# IoT_PCB.net
KiCad netlist of a schematic drawn in EAGLE
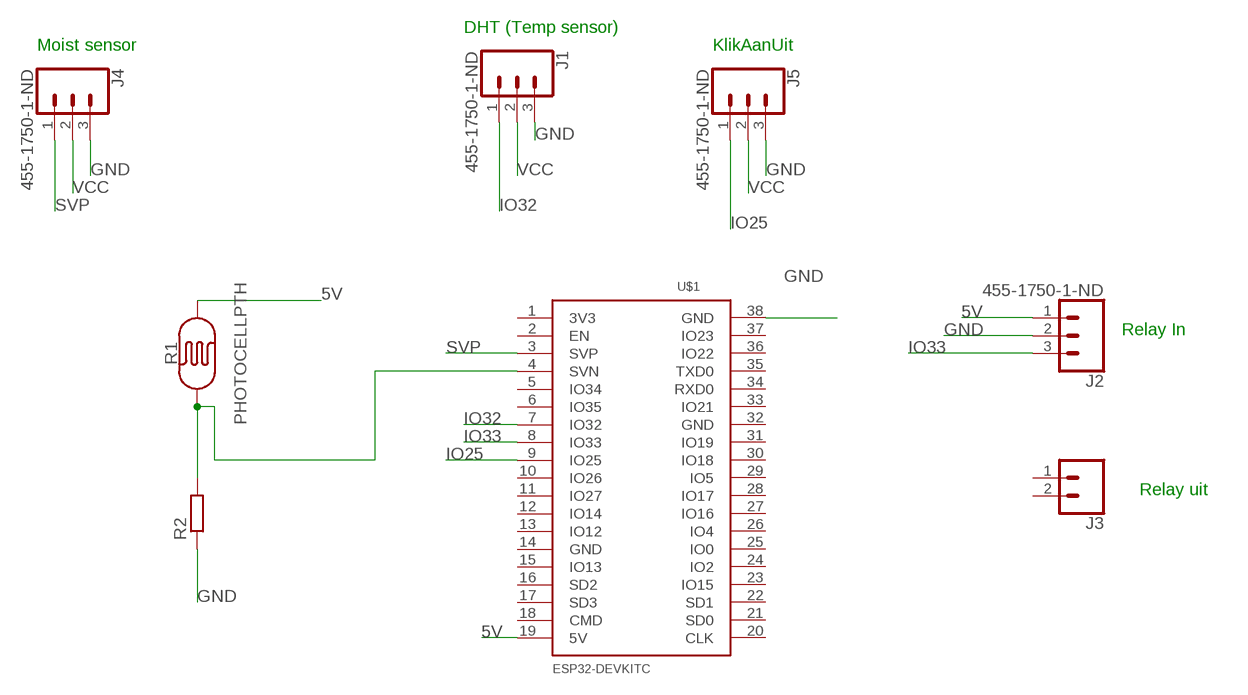
[diagram p0: schematic, sheet 1]

(export (version "E")
  (design (tool "Eeschema 10.0.6"))
  (components
    (comp (ref "J1")
      (value "455-1750-1-ND")
      (footprint "eagle-import:1X03")
      (libsource (lib "eagle-import") (part "CONN_03"))
    )
    (comp (ref "J2")
      (value "455-1750-1-ND")
      (footprint "eagle-import:1X03")
      (libsource (lib "eagle-import") (part "CONN_03"))
    )
    (comp (ref "J3")
      (value "CONN_02")
      (footprint "eagle-import:1X02")
      (libsource (lib "eagle-import") (part "CONN_02"))
    )
    (comp (ref "J4")
      (value "455-1750-1-ND")
      (footprint "eagle-import:1X03")
      (libsource (lib "eagle-import") (part "CONN_03"))
    )
    (comp (ref "J5")
      (value "455-1750-1-ND")
      (footprint "eagle-import:1X03")
      (libsource (lib "eagle-import") (part "CONN_03"))
    )
    (comp (ref "R1")
      (value "PHOTOCELLPTH")
      (footprint "eagle-import:PHOTOCELL")
      (libsource (lib "eagle-import") (part "PHOTOCELLPTH"))
    )
    (comp (ref "R2")
      (value "R-EU_0207/10")
      (footprint "eagle-import:0207_10")
      (libsource (lib "eagle-import") (part "R-EU_0207/10"))
    )
    (comp (ref "U$1")
      (value "ESP32DEVKITC")
      (footprint "eagle-import:ESP32-DEVKITC")
      (libsource (lib "eagle-import") (part "ESP32DEVKITC"))
    )
  )
  (nets
    (net (code "1") (name "/5V") (class "Default")
      (node (ref "J2") (pin "1") (pinfunction "1_1") (pintype "passive"))
      (node (ref "R1") (pin "2") (pinfunction "P$2_2") (pintype "bidirectional"))
      (node (ref "U$1") (pin "19") (pinfunction "5V_19") (pintype "bidirectional"))
    )
    (net (code "2") (name "/GND") (class "Default")
      (node (ref "J1") (pin "3") (pinfunction "3_3") (pintype "passive"))
      (node (ref "J2") (pin "2") (pinfunction "2_2") (pintype "passive"))
      (node (ref "J4") (pin "3") (pinfunction "3_3") (pintype "passive"))
      (node (ref "J5") (pin "3") (pinfunction "3_3") (pintype "passive"))
      (node (ref "R2") (pin "1") (pinfunction "1_1") (pintype "passive"))
      (node (ref "U$1") (pin "38") (pinfunction "GND_38") (pintype "bidirectional"))
    )
    (net (code "3") (name "/IO25") (class "Default")
      (node (ref "J5") (pin "1") (pinfunction "1_1") (pintype "passive"))
      (node (ref "U$1") (pin "9") (pinfunction "IO25_9") (pintype "bidirectional"))
    )
    (net (code "4") (name "/IO32") (class "Default")
      (node (ref "J1") (pin "1") (pinfunction "1_1") (pintype "passive"))
      (node (ref "U$1") (pin "7") (pinfunction "IO32_7") (pintype "bidirectional"))
    )
    (net (code "5") (name "/IO33") (class "Default")
      (node (ref "J2") (pin "3") (pinfunction "3_3") (pintype "passive"))
      (node (ref "U$1") (pin "8") (pinfunction "IO33_8") (pintype "bidirectional"))
    )
    (net (code "6") (name "/SVP") (class "Default")
      (node (ref "J4") (pin "1") (pinfunction "1_1") (pintype "passive"))
      (node (ref "U$1") (pin "3") (pinfunction "SVP_3") (pintype "bidirectional"))
    )
    (net (code "7") (name "/VCC") (class "Default")
      (node (ref "J1") (pin "2") (pinfunction "2_2") (pintype "passive"))
      (node (ref "J4") (pin "2") (pinfunction "2_2") (pintype "passive"))
      (node (ref "J5") (pin "2") (pinfunction "2_2") (pintype "passive"))
    )
    (net (code "8") (name "Net-(R1-P$1)") (class "Default")
      (node (ref "R1") (pin "1") (pinfunction "P$1_1") (pintype "bidirectional"))
      (node (ref "R2") (pin "2") (pinfunction "2_2") (pintype "passive"))
      (node (ref "U$1") (pin "4") (pinfunction "SVN_4") (pintype "bidirectional"))
    )
    (net (code "9") (name "unconnected-(J3-Pad1)") (class "Default")
      (node (ref "J3") (pin "1") (pinfunction "1_1") (pintype "passive"))
    )
    (net (code "10") (name "unconnected-(J3-Pad2)") (class "Default")
      (node (ref "J3") (pin "2") (pinfunction "2_2") (pintype "passive"))
    )
    (net (code "11") (name "unconnected-(U$1-3V3-Pad1)") (class "Default")
      (node (ref "U$1") (pin "1") (pinfunction "3V3_1") (pintype "bidirectional"))
    )
    (net (code "12") (name "unconnected-(U$1-CLK-Pad20)") (class "Default")
      (node (ref "U$1") (pin "20") (pinfunction "CLK_20") (pintype "bidirectional"))
    )
    (net (code "13") (name "unconnected-(U$1-CMD-Pad18)") (class "Default")
      (node (ref "U$1") (pin "18") (pinfunction "CMD_18") (pintype "bidirectional"))
    )
    (net (code "14") (name "unconnected-(U$1-EN-Pad2)") (class "Default")
      (node (ref "U$1") (pin "2") (pinfunction "EN_2") (pintype "bidirectional"))
    )
    (net (code "15") (name "unconnected-(U$1-GND-Pad14)") (class "Default")
      (node (ref "U$1") (pin "14") (pinfunction "GND_14") (pintype "bidirectional"))
    )
    (net (code "16") (name "unconnected-(U$1-GND-Pad32)") (class "Default")
      (node (ref "U$1") (pin "32") (pinfunction "GND_32") (pintype "bidirectional"))
    )
    (net (code "17") (name "unconnected-(U$1-IO0-Pad25)") (class "Default")
      (node (ref "U$1") (pin "25") (pinfunction "IO0_25") (pintype "bidirectional"))
    )
    (net (code "18") (name "unconnected-(U$1-IO2-Pad24)") (class "Default")
      (node (ref "U$1") (pin "24") (pinfunction "IO2_24") (pintype "bidirectional"))
    )
    (net (code "19") (name "unconnected-(U$1-IO4-Pad26)") (class "Default")
      (node (ref "U$1") (pin "26") (pinfunction "IO4_26") (pintype "bidirectional"))
    )
    (net (code "20") (name "unconnected-(U$1-IO5-Pad29)") (class "Default")
      (node (ref "U$1") (pin "29") (pinfunction "IO5_29") (pintype "bidirectional"))
    )
    (net (code "21") (name "unconnected-(U$1-IO12-Pad13)") (class "Default")
      (node (ref "U$1") (pin "13") (pinfunction "IO12_13") (pintype "bidirectional"))
    )
    (net (code "22") (name "unconnected-(U$1-IO13-Pad15)") (class "Default")
      (node (ref "U$1") (pin "15") (pinfunction "IO13_15") (pintype "bidirectional"))
    )
    (net (code "23") (name "unconnected-(U$1-IO14-Pad12)") (class "Default")
      (node (ref "U$1") (pin "12") (pinfunction "IO14_12") (pintype "bidirectional"))
    )
    (net (code "24") (name "unconnected-(U$1-IO15-Pad23)") (class "Default")
      (node (ref "U$1") (pin "23") (pinfunction "IO15_23") (pintype "bidirectional"))
    )
    (net (code "25") (name "unconnected-(U$1-IO16-Pad27)") (class "Default")
      (node (ref "U$1") (pin "27") (pinfunction "IO16_27") (pintype "bidirectional"))
    )
    (net (code "26") (name "unconnected-(U$1-IO17-Pad28)") (class "Default")
      (node (ref "U$1") (pin "28") (pinfunction "IO17_28") (pintype "bidirectional"))
    )
    (net (code "27") (name "unconnected-(U$1-IO18-Pad30)") (class "Default")
      (node (ref "U$1") (pin "30") (pinfunction "IO18_30") (pintype "bidirectional"))
    )
    (net (code "28") (name "unconnected-(U$1-IO19-Pad31)") (class "Default")
      (node (ref "U$1") (pin "31") (pinfunction "IO19_31") (pintype "bidirectional"))
    )
    (net (code "29") (name "unconnected-(U$1-IO21-Pad33)") (class "Default")
      (node (ref "U$1") (pin "33") (pinfunction "IO21_33") (pintype "bidirectional"))
    )
    (net (code "30") (name "unconnected-(U$1-IO22-Pad36)") (class "Default")
      (node (ref "U$1") (pin "36") (pinfunction "IO22_36") (pintype "bidirectional"))
    )
    (net (code "31") (name "unconnected-(U$1-IO23-Pad37)") (class "Default")
      (node (ref "U$1") (pin "37") (pinfunction "IO23_37") (pintype "bidirectional"))
    )
    (net (code "32") (name "unconnected-(U$1-IO26-Pad10)") (class "Default")
      (node (ref "U$1") (pin "10") (pinfunction "IO26_10") (pintype "bidirectional"))
    )
    (net (code "33") (name "unconnected-(U$1-IO27-Pad11)") (class "Default")
      (node (ref "U$1") (pin "11") (pinfunction "IO27_11") (pintype "bidirectional"))
    )
    (net (code "34") (name "unconnected-(U$1-IO34-Pad5)") (class "Default")
      (node (ref "U$1") (pin "5") (pinfunction "IO34_5") (pintype "bidirectional"))
    )
    (net (code "35") (name "unconnected-(U$1-IO35-Pad6)") (class "Default")
      (node (ref "U$1") (pin "6") (pinfunction "IO35_6") (pintype "bidirectional"))
    )
    (net (code "36") (name "unconnected-(U$1-RXD0-Pad34)") (class "Default")
      (node (ref "U$1") (pin "34") (pinfunction "RXD0_34") (pintype "bidirectional"))
    )
    (net (code "37") (name "unconnected-(U$1-SD0-Pad21)") (class "Default")
      (node (ref "U$1") (pin "21") (pinfunction "SD0_21") (pintype "bidirectional"))
    )
    (net (code "38") (name "unconnected-(U$1-SD1-Pad22)") (class "Default")
      (node (ref "U$1") (pin "22") (pinfunction "SD1_22") (pintype "bidirectional"))
    )
    (net (code "39") (name "unconnected-(U$1-SD2-Pad16)") (class "Default")
      (node (ref "U$1") (pin "16") (pinfunction "SD2_16") (pintype "bidirectional"))
    )
    (net (code "40") (name "unconnected-(U$1-SD3-Pad17)") (class "Default")
      (node (ref "U$1") (pin "17") (pinfunction "SD3_17") (pintype "bidirectional"))
    )
    (net (code "41") (name "unconnected-(U$1-TXD0-Pad35)") (class "Default")
      (node (ref "U$1") (pin "35") (pinfunction "TXD0_35") (pintype "bidirectional"))
    )
  )
)
